# capacitive_touch_board_RIGHT.net
KiCad netlist of a schematic drawn in EAGLE
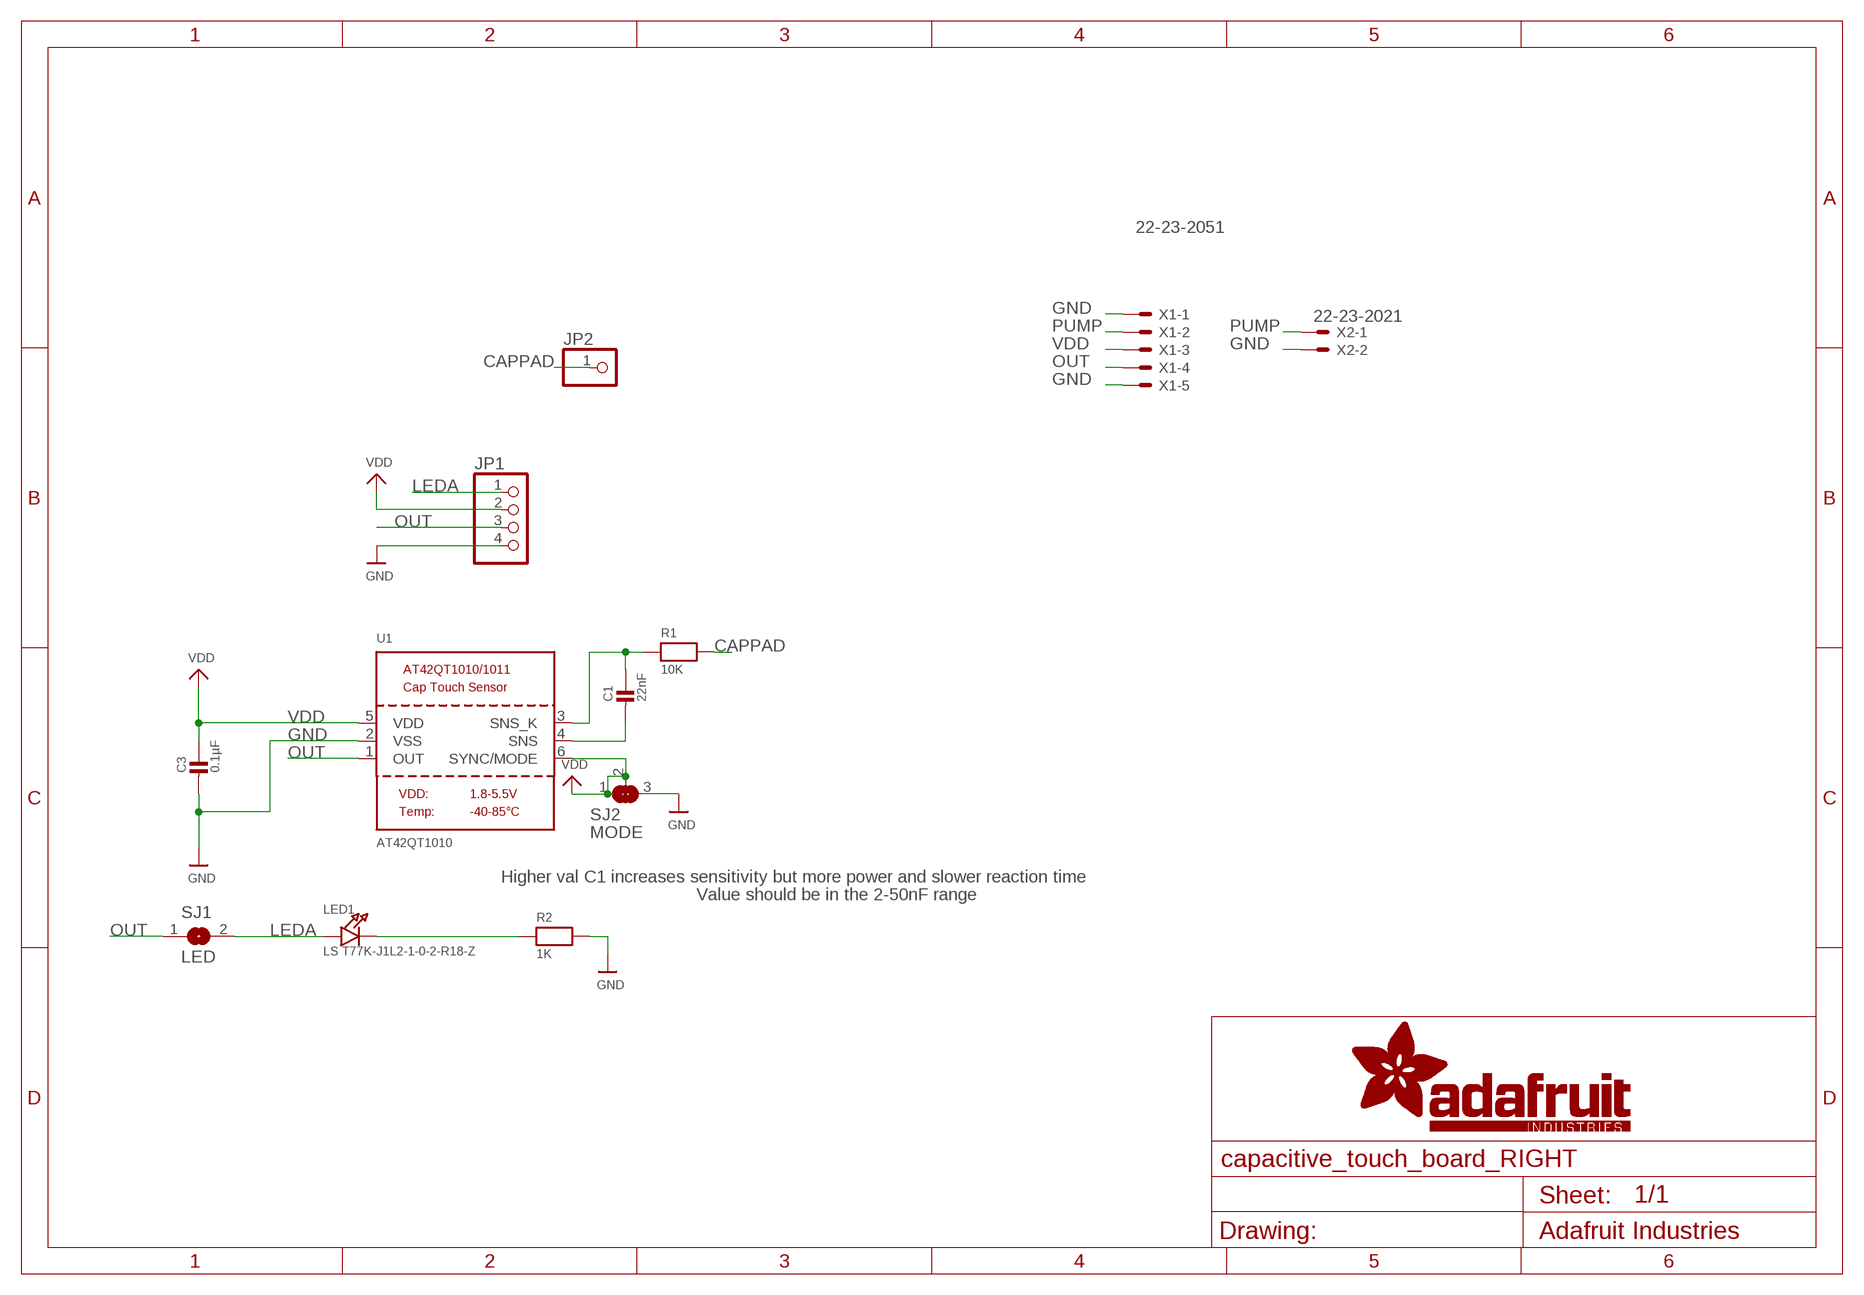
[diagram p0: schematic, sheet 1]

(export (version "E")
  (design (tool "Eeschema 10.0.6"))
  (components
    (comp (ref "C1")
      (value "22nF")
      (footprint "eagle-import:_0805")
      (libsource (lib "eagle-import") (part "CAP_CERAMIC_0805"))
    )
    (comp (ref "C3")
      (value "0.1µF")
      (footprint "eagle-import:_0805")
      (libsource (lib "eagle-import") (part "CAP_CERAMIC_0805"))
    )
    (comp (ref "JP1")
      (value "HEADER-1X476MIL")
      (footprint "eagle-import:1X04_ROUND_76")
      (libsource (lib "eagle-import") (part "HEADER-1X476MIL"))
    )
    (comp (ref "JP2")
      (value "PINHD-1X1")
      (footprint "eagle-import:1X01")
      (libsource (lib "eagle-import") (part "PINHD-1X1"))
    )
    (comp (ref "LED1")
      (value "LS T77K-J1L2-1-0-2-R18-Z")
      (footprint "eagle-import:PLCC2_REVMOUNT")
      (libsource (lib "eagle-import") (part "LEDPLCC2_REV"))
    )
    (comp (ref "R1")
      (value "10K")
      (footprint "eagle-import:_0805")
      (libsource (lib "eagle-import") (part "RESISTOR_0805"))
    )
    (comp (ref "R2")
      (value "1K")
      (footprint "eagle-import:_0805")
      (libsource (lib "eagle-import") (part "RESISTOR_0805"))
    )
    (comp (ref "SJ1")
      (value "LED")
      (footprint "eagle-import:SOLDERJUMPER_CLOSEDWIRE")
      (libsource (lib "eagle-import") (part "SOLDERJUMPERCLOSED"))
    )
    (comp (ref "SJ2")
      (value "MODE")
      (footprint "eagle-import:SOLDERJUMPER_2WAY_OPEN_NOPASTE")
      (libsource (lib "eagle-import") (part "SOLDERJUMPER_2WAY"))
    )
    (comp (ref "U1")
      (value "AT42QT1010")
      (footprint "eagle-import:SOT23-6")
      (libsource (lib "eagle-import") (part "AT42QT1010/1"))
    )
    (comp (ref "X1")
      (value "22-23-2051")
      (footprint "eagle-import:22-23-2051")
      (fields (field (name "MF") "MOLEX"))
      (libsource (lib "eagle-import") (part "22-23-2051"))
    )
    (comp (ref "X2")
      (value "22-23-2021")
      (footprint "eagle-import:22-23-2021")
      (fields (field (name "MF") "MOLEX"))
      (libsource (lib "eagle-import") (part "22-23-2021"))
    )
  )
  (nets
    (net (code "1") (name "/CAPPAD") (class "Default")
      (node (ref "JP2") (pin "1") (pinfunction "1_1") (pintype "passive"))
      (node (ref "R1") (pin "2") (pinfunction "2_2") (pintype "passive"))
    )
    (net (code "2") (name "/LEDA") (class "Default")
      (node (ref "JP1") (pin "1") (pinfunction "1_1") (pintype "passive"))
      (node (ref "LED1") (pin "A") (pinfunction "A_A") (pintype "passive"))
      (node (ref "SJ1") (pin "2") (pinfunction "2_2") (pintype "passive"))
    )
    (net (code "3") (name "/OUT") (class "Default")
      (node (ref "JP1") (pin "3") (pinfunction "3_3") (pintype "passive"))
      (node (ref "SJ1") (pin "1") (pinfunction "1_1") (pintype "passive"))
      (node (ref "U1") (pin "1") (pinfunction "OUT_1") (pintype "output"))
      (node (ref "X1") (pin "4") (pinfunction "S_4") (pintype "passive"))
    )
    (net (code "4") (name "/PUMP") (class "Default")
      (node (ref "X1") (pin "2") (pinfunction "S_2") (pintype "passive"))
      (node (ref "X2") (pin "1") (pinfunction "S_1") (pintype "passive"))
    )
    (net (code "5") (name "GND") (class "Default")
      (node (ref "C3") (pin "2") (pinfunction "P$2_2") (pintype "passive"))
      (node (ref "JP1") (pin "4") (pinfunction "4_4") (pintype "passive"))
      (node (ref "R2") (pin "2") (pinfunction "2_2") (pintype "passive"))
      (node (ref "SJ2") (pin "3") (pinfunction "3_3") (pintype "passive"))
      (node (ref "U1") (pin "2") (pinfunction "VSS_2") (pintype "power_in"))
      (node (ref "X1") (pin "1") (pinfunction "S_1") (pintype "passive"))
      (node (ref "X1") (pin "5") (pinfunction "S_5") (pintype "passive"))
      (node (ref "X2") (pin "2") (pinfunction "S_2") (pintype "passive"))
    )
    (net (code "6") (name "Net-(C1-P$1)") (class "Default")
      (node (ref "C1") (pin "1") (pinfunction "P$1_1") (pintype "passive"))
      (node (ref "R1") (pin "1") (pinfunction "1_1") (pintype "passive"))
      (node (ref "U1") (pin "3") (pinfunction "SNS_K_3") (pintype "bidirectional"))
    )
    (net (code "7") (name "Net-(C1-P$2)") (class "Default")
      (node (ref "C1") (pin "2") (pinfunction "P$2_2") (pintype "passive"))
      (node (ref "U1") (pin "4") (pinfunction "SNS_4") (pintype "bidirectional"))
    )
    (net (code "8") (name "Net-(LED1-C)") (class "Default")
      (node (ref "LED1") (pin "K") (pinfunction "C_K") (pintype "passive"))
      (node (ref "R2") (pin "1") (pinfunction "1_1") (pintype "passive"))
    )
    (net (code "9") (name "VDD") (class "Default")
      (node (ref "C3") (pin "1") (pinfunction "P$1_1") (pintype "passive"))
      (node (ref "JP1") (pin "2") (pinfunction "2_2") (pintype "passive"))
      (node (ref "SJ2") (pin "1") (pinfunction "1_1") (pintype "passive"))
      (node (ref "SJ2") (pin "2") (pinfunction "2_2") (pintype "passive"))
      (node (ref "U1") (pin "5") (pinfunction "VDD_5") (pintype "power_in"))
      (node (ref "U1") (pin "6") (pinfunction "SYNC/MODE_6") (pintype "input"))
      (node (ref "X1") (pin "3") (pinfunction "S_3") (pintype "passive"))
    )
  )
)
